# Sheet1.net
KiCad netlist of a schematic drawn in Altium Designer
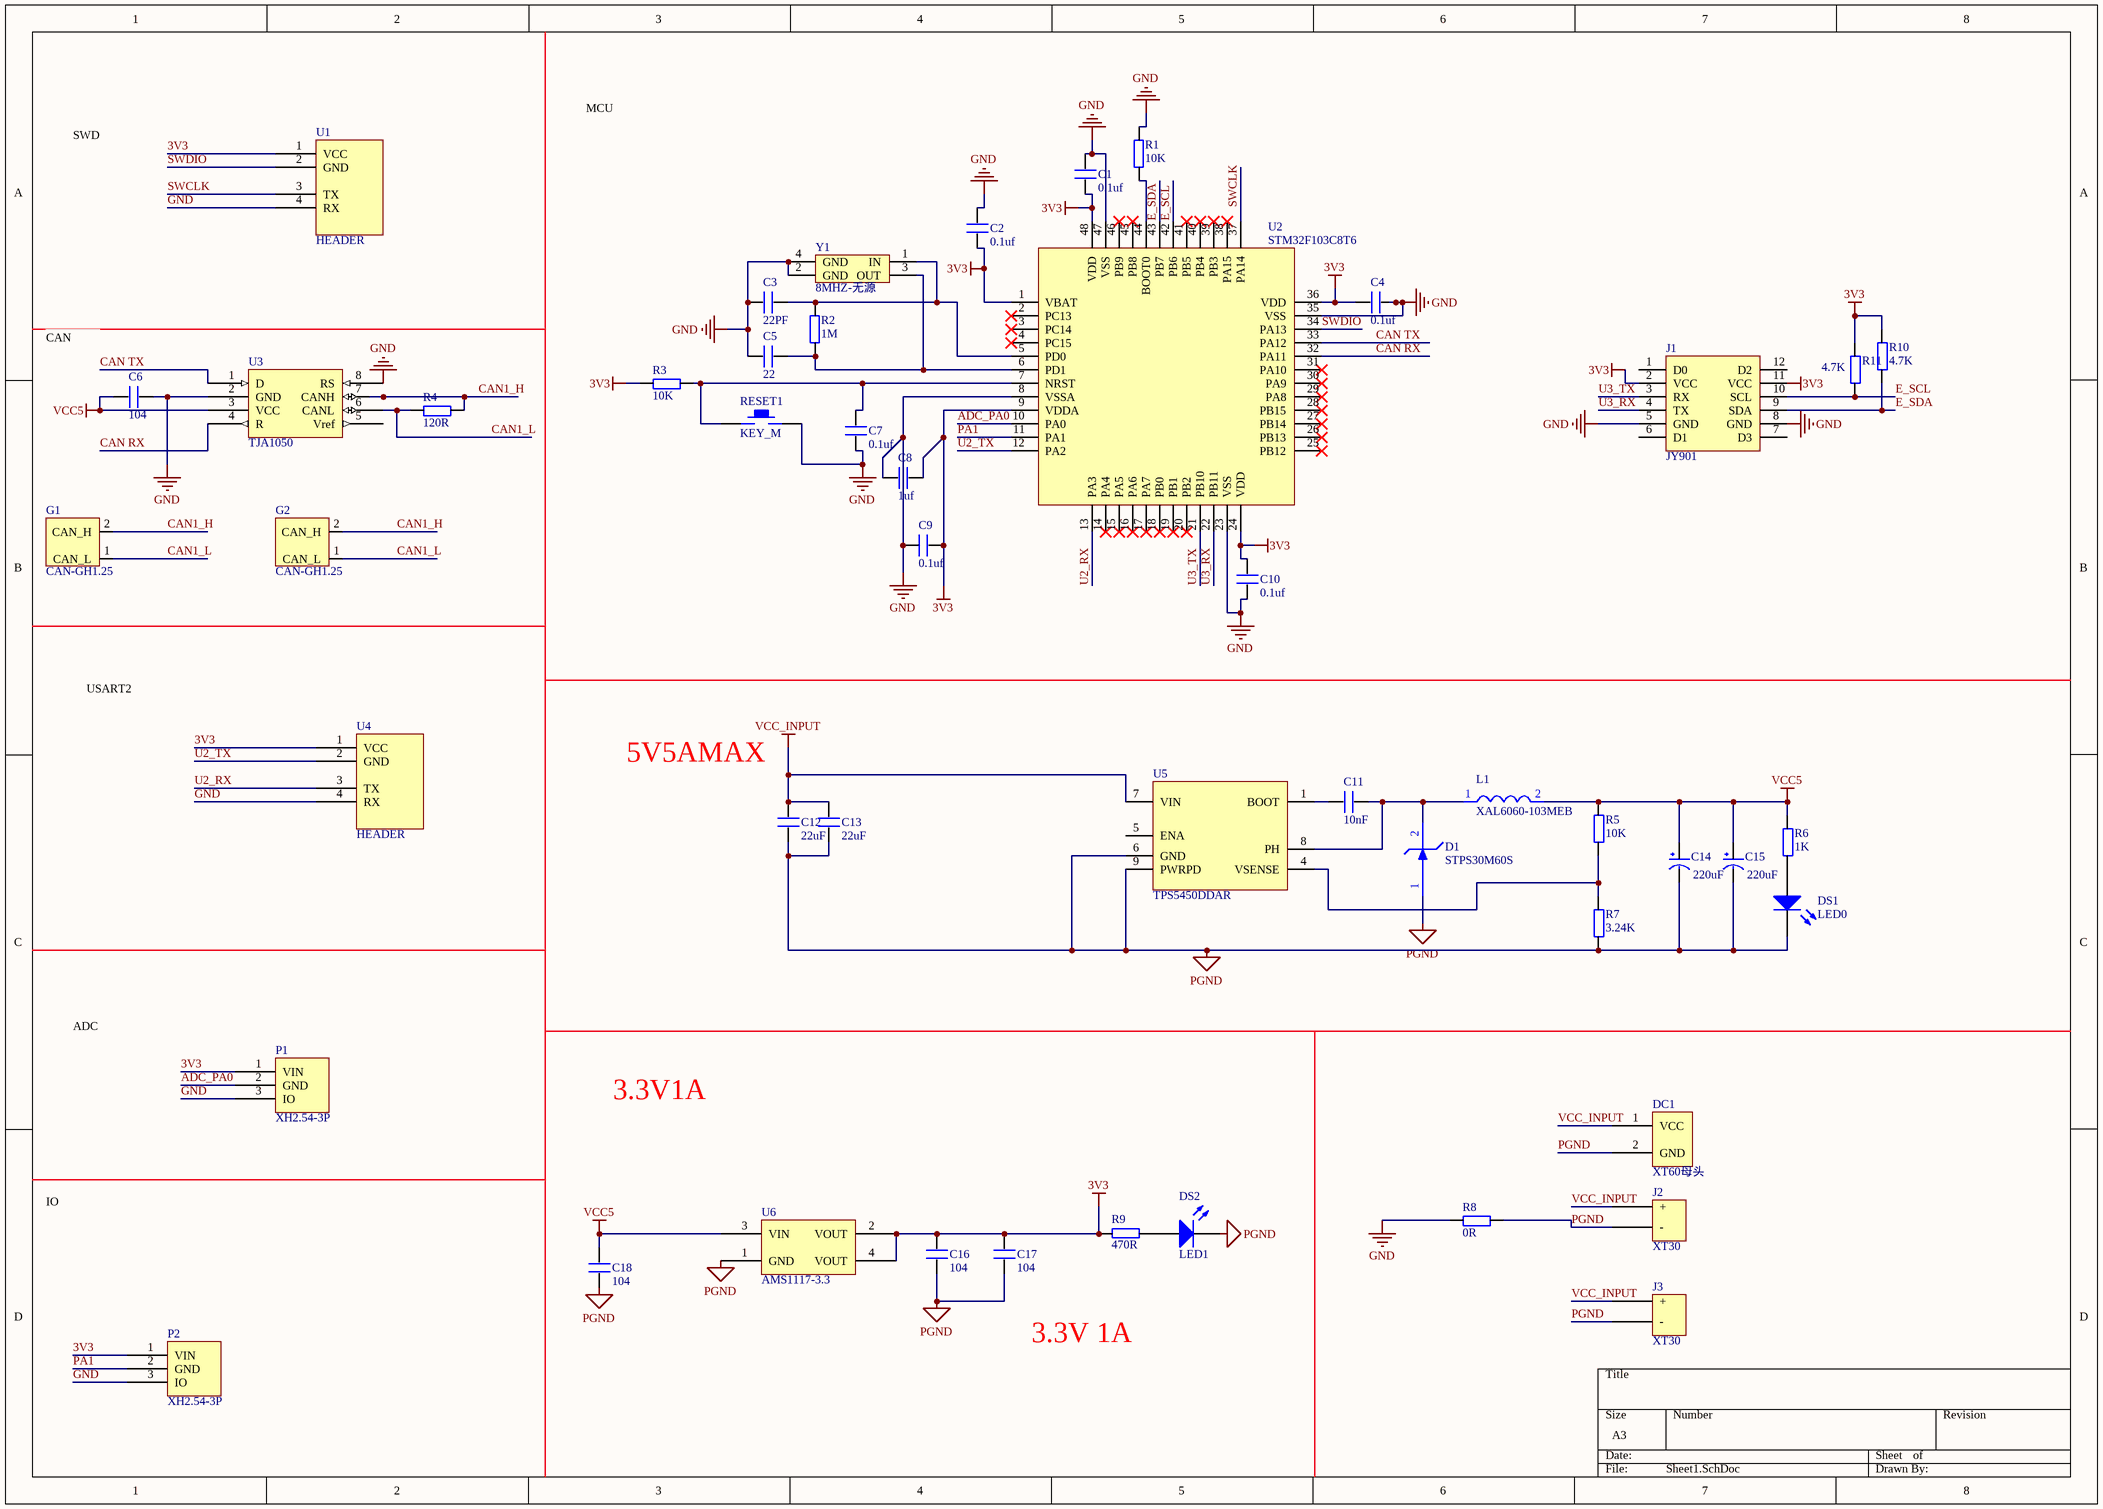
[diagram p0: Sheet1.SchDoc]

(export (version "E")
  (design (tool "Eeschema 10.0.6"))
  (components
    (comp (ref "C1") (value "0.1uf") (footprint "0603P") (libsource (lib "Explorer STM32F407封装库") (part "C")))
    (comp (ref "C2") (value "0.1uf") (footprint "0603P") (libsource (lib "Explorer STM32F407封装库") (part "C")))
    (comp (ref "C3") (value "22PF") (footprint "0603P") (libsource (lib "Explorer STM32F407封装库") (part "C")))
    (comp (ref "C4") (value "0.1uf") (footprint "0603P") (libsource (lib "Explorer STM32F407封装库") (part "C")))
    (comp (ref "C5") (value "22") (footprint "0603P") (libsource (lib "Explorer STM32F407封装库") (part "C")))
    (comp (ref "C6") (value "104") (footprint "0603P") (libsource (lib "Explorer STM32F407封装库") (part "C")))
    (comp (ref "C7") (value "0.1uf") (footprint "0603P") (libsource (lib "Explorer STM32F407封装库") (part "C")))
    (comp (ref "C8") (value "1uf") (footprint "0603P") (libsource (lib "Explorer STM32F407封装库") (part "C")))
    (comp (ref "C9") (value "0.1uf") (footprint "0603P") (libsource (lib "Explorer STM32F407封装库") (part "C")))
    (comp (ref "C10")
      (value "0.1uf")
      (footprint "0603P")
      (libsource (lib "Explorer STM32F407封装库") (part "C"))
    )
    (comp (ref "C11")
      (value "10nF")
      (footprint "0603P")
      (libsource (lib "Explorer STM32F407封装库_SCH") (part "C"))
    )
    (comp (ref "C12")
      (value "22uF")
      (footprint "0603P")
      (libsource (lib "Explorer STM32F407封装库_SCH") (part "C"))
    )
    (comp (ref "C13")
      (value "22uF")
      (footprint "0603P")
      (libsource (lib "Explorer STM32F407封装库_SCH") (part "C"))
    )
    (comp (ref "C14")
      (value "220uF")
      (footprint "CC6.56.5")
      (libsource (lib "Explorer STM32F407封装库") (part "CAP"))
    )
    (comp (ref "C15")
      (value "220uF")
      (footprint "CC6.56.5")
      (libsource (lib "Explorer STM32F407封装库") (part "CAP"))
    )
    (comp (ref "C16")
      (value "104")
      (footprint "0603P")
      (libsource (lib "Explorer STM32F407封装库_SCH") (part "C"))
    )
    (comp (ref "C17")
      (value "104")
      (footprint "0603P")
      (libsource (lib "Explorer STM32F407封装库_SCH") (part "C"))
    )
    (comp (ref "C18")
      (value "104")
      (footprint "0603P")
      (libsource (lib "Explorer STM32F407封装库_SCH") (part "C"))
    )
    (comp (ref "D1")
      (value "STPS30M60S")
      (footprint "STPS30M60S")
      (libsource (lib "SCHlib") (part "STPS30M60S"))
    )
    (comp (ref "DC1") (value "XT60母头") (footprint "XT60-母头") (libsource (lib "羽毛球团队") (part "XT60-母头")))
    (comp (ref "DS1")
      (value "LED0")
      (footprint "LED-0603-hm")
      (description "Typical RED, GREEN, YELLOW, AMBER GaAs LED")
      (fields (field (name "PUBLISHER") "Altium Limited"))
      (libsource (lib "Explorer STM32F407封装库") (part "LED2"))
    )
    (comp (ref "DS2")
      (value "LED1")
      (footprint "LED-0603-hm")
      (description "Typical RED, GREEN, YELLOW, AMBER GaAs LED")
      (fields (field (name "PUBLISHER") "Altium Limited"))
      (libsource (lib "Explorer STM32F407封装库") (part "LED2"))
    )
    (comp (ref "G1")
      (value "CAN-GH1.25")
      (footprint "GH1.25_1*2_lishi")
      (libsource (lib "SCHlib") (part "GH1.25-CAN"))
    )
    (comp (ref "G2")
      (value "CAN-GH1.25")
      (footprint "GH1.25_1*2_lishi")
      (libsource (lib "SCHlib") (part "GH1.25-CAN"))
    )
    (comp (ref "J1") (value "JY901") (footprint "JY901") (libsource (lib "Mini_Blimp") (part "JY901-PAD")))
    (comp (ref "J2") (value "XT30") (footprint "XT30") (libsource (lib "SCHlib") (part "XT30")))
    (comp (ref "J3") (value "XT30") (footprint "XT30") (libsource (lib "SCHlib") (part "XT30")))
    (comp (ref "L1")
      (value "XAL6060-103MEB")
      (footprint "XAL6060-103MEB")
      (libsource (lib "SCHlib") (part "贴片电感"))
    )
    (comp (ref "P1")
      (value "XH2.54-3P")
      (footprint "XH2.54插座-3P")
      (libsource (lib "羽毛球团队") (part "XH2.54插座-3P"))
    )
    (comp (ref "P2")
      (value "XH2.54-3P")
      (footprint "XH2.54插座-3P")
      (libsource (lib "羽毛球团队") (part "XH2.54插座-3P"))
    )
    (comp (ref "R1") (value "10K") (footprint "0603P") (libsource (lib "Explorer STM32F407封装库") (part "R")))
    (comp (ref "R2") (value "1M") (footprint "0603P") (libsource (lib "Explorer STM32F407封装库") (part "R")))
    (comp (ref "R3") (value "10K") (footprint "0603P") (libsource (lib "Explorer STM32F407封装库") (part "R")))
    (comp (ref "R4") (value "120R") (footprint "0603P") (libsource (lib "Explorer STM32F407封装库") (part "R")))
    (comp (ref "R5")
      (value "10K")
      (footprint "0603P")
      (libsource (lib "Explorer STM32F407封装库_SCH") (part "R"))
    )
    (comp (ref "R6")
      (value "1K")
      (footprint "0603P")
      (libsource (lib "Explorer STM32F407封装库_SCH") (part "R"))
    )
    (comp (ref "R7")
      (value "3.24K")
      (footprint "0603P")
      (libsource (lib "Explorer STM32F407封装库_SCH") (part "R"))
    )
    (comp (ref "R8") (value "0R") (footprint "0603P") (libsource (lib "Explorer STM32F407封装库") (part "R")))
    (comp (ref "R9")
      (value "470R")
      (footprint "0603P")
      (libsource (lib "Explorer STM32F407封装库_SCH") (part "R"))
    )
    (comp (ref "R10") (value "4.7K") (footprint "0603P") (libsource (lib "Explorer STM32F407封装库") (part "R")))
    (comp (ref "R11") (value "4.7K") (footprint "0603P") (libsource (lib "Explorer STM32F407封装库") (part "R")))
    (comp (ref "RESET1")
      (value "KEY_M")
      (footprint "KEY_M")
      (libsource (lib "Explorer STM32F407封装库_SCH") (part "KEY_M"))
    )
    (comp (ref "U1")
      (value "HEADER")
      (footprint "XH2.54插座-4P")
      (libsource (lib "羽毛球团队") (part "XH2.54插座-4P"))
    )
    (comp (ref "U2")
      (value "STM32F103C8T6")
      (footprint "LQFP-48_7x7x05P")
      (libsource (lib "RoboFly") (part "STM32F103C8T6"))
    )
    (comp (ref "U3")
      (value "TJA1050")
      (footprint "SOP-8")
      (libsource (lib "Explorer STM32F407封装库") (part "SN65HVD230D"))
    )
    (comp (ref "U4")
      (value "HEADER")
      (footprint "XH2.54插座-4P")
      (libsource (lib "羽毛球团队") (part "XH2.54插座-4P"))
    )
    (comp (ref "U5") (value "TPS5450DDAR") (footprint "TPS5450") (libsource (lib "SCHlib") (part "TPS5450")))
    (comp (ref "U6") (value "AMS1117-3.3") (footprint "SOT223") (libsource (lib "74hc595") (part "AMS1117")))
    (comp (ref "Y1")
      (value "8MHZ-无源")
      (footprint "XTAL3225   无源")
      (libsource (lib "SCHlib") (part "XTAL-3225"))
    )
  )
  (nets
    (net (code "1") (name "/ADC_PA0") (class "Default")
      (node (ref "P1") (pin "2") (pinfunction "GND_2") (pintype "passive"))
      (node (ref "U2") (pin "10") (pinfunction "PA0_10") (pintype "passive"))
    )
    (net (code "2") (name "/CAN RX") (class "Default")
      (node (ref "U2") (pin "32") (pinfunction "PA11_32") (pintype "passive"))
      (node (ref "U3") (pin "4") (pinfunction "R_4") (pintype "output"))
    )
    (net (code "3") (name "/CAN TX") (class "Default")
      (node (ref "U2") (pin "33") (pinfunction "PA12_33") (pintype "passive"))
      (node (ref "U3") (pin "1") (pinfunction "D_1") (pintype "input"))
    )
    (net (code "4") (name "/CAN1_H") (class "Default")
      (node (ref "G1") (pin "2") (pinfunction "CAN_H_2") (pintype "passive"))
      (node (ref "G2") (pin "2") (pinfunction "CAN_H_2") (pintype "passive"))
      (node (ref "R4") (pin "2") (pintype "passive"))
      (node (ref "U3") (pin "7") (pinfunction "CANH_7") (pintype "bidirectional"))
    )
    (net (code "5") (name "/CAN1_L") (class "Default")
      (node (ref "G1") (pin "1") (pinfunction "CAN_L_1") (pintype "passive"))
      (node (ref "G2") (pin "1") (pinfunction "CAN_L_1") (pintype "passive"))
      (node (ref "R4") (pin "1") (pintype "passive"))
      (node (ref "U3") (pin "6") (pinfunction "CANL_6") (pintype "bidirectional"))
    )
    (net (code "6") (name "/E_SCL") (class "Default")
      (node (ref "J1") (pin "10") (pinfunction "SCL_10") (pintype "passive"))
      (node (ref "R11") (pin "1") (pintype "passive"))
      (node (ref "U2") (pin "42") (pinfunction "PB6_42") (pintype "passive"))
    )
    (net (code "7") (name "/E_SDA") (class "Default")
      (node (ref "J1") (pin "9") (pinfunction "SDA_9") (pintype "passive"))
      (node (ref "R10") (pin "1") (pintype "passive"))
      (node (ref "U2") (pin "43") (pinfunction "PB7_43") (pintype "passive"))
    )
    (net (code "8") (name "/PA1") (class "Default")
      (node (ref "P2") (pin "2") (pinfunction "GND_2") (pintype "passive"))
      (node (ref "U2") (pin "11") (pinfunction "PA1_11") (pintype "passive"))
    )
    (net (code "9") (name "/SWCLK") (class "Default")
      (node (ref "U1") (pin "3") (pinfunction "TX_3") (pintype "passive"))
      (node (ref "U2") (pin "37") (pinfunction "PA14_37") (pintype "passive"))
    )
    (net (code "10") (name "/SWDIO") (class "Default")
      (node (ref "U1") (pin "2") (pinfunction "GND_2") (pintype "passive"))
      (node (ref "U2") (pin "34") (pinfunction "PA13_34") (pintype "passive"))
    )
    (net (code "11") (name "/U2_RX") (class "Default")
      (node (ref "U2") (pin "13") (pinfunction "PA3_13") (pintype "passive"))
      (node (ref "U4") (pin "3") (pinfunction "TX_3") (pintype "passive"))
    )
    (net (code "12") (name "/U2_TX") (class "Default")
      (node (ref "U2") (pin "12") (pinfunction "PA2_12") (pintype "passive"))
      (node (ref "U4") (pin "2") (pinfunction "GND_2") (pintype "passive"))
    )
    (net (code "13") (name "/U3_RX") (class "Default")
      (node (ref "J1") (pin "4") (pinfunction "TX_4") (pintype "passive"))
      (node (ref "U2") (pin "22") (pinfunction "PB11_22") (pintype "passive"))
    )
    (net (code "14") (name "/U3_TX") (class "Default")
      (node (ref "J1") (pin "3") (pinfunction "RX_3") (pintype "passive"))
      (node (ref "U2") (pin "21") (pinfunction "PB10_21") (pintype "passive"))
    )
    (net (code "15") (name "3V3") (class "Default")
      (node (ref "C1") (pin "1") (pintype "passive"))
      (node (ref "C10") (pin "2") (pintype "passive"))
      (node (ref "C16") (pin "2") (pintype "passive"))
      (node (ref "C17") (pin "2") (pintype "passive"))
      (node (ref "C2") (pin "1") (pintype "passive"))
      (node (ref "C4") (pin "2") (pintype "passive"))
      (node (ref "C8") (pin "1") (pintype "passive"))
      (node (ref "C9") (pin "1") (pintype "passive"))
      (node (ref "J1") (pin "11") (pinfunction "VCC_11") (pintype "passive"))
      (node (ref "J1") (pin "2") (pinfunction "VCC_2") (pintype "passive"))
      (node (ref "P1") (pin "1") (pinfunction "VIN_1") (pintype "passive"))
      (node (ref "P2") (pin "1") (pinfunction "VIN_1") (pintype "passive"))
      (node (ref "R10") (pin "2") (pintype "passive"))
      (node (ref "R11") (pin "2") (pintype "passive"))
      (node (ref "R3") (pin "1") (pintype "passive"))
      (node (ref "R9") (pin "2") (pintype "passive"))
      (node (ref "U1") (pin "1") (pinfunction "VCC_1") (pintype "passive"))
      (node (ref "U2") (pin "1") (pinfunction "VBAT_1") (pintype "passive"))
      (node (ref "U2") (pin "24") (pinfunction "VDD_24") (pintype "passive"))
      (node (ref "U2") (pin "36") (pinfunction "VDD_36") (pintype "passive"))
      (node (ref "U2") (pin "48") (pinfunction "VDD_48") (pintype "passive"))
      (node (ref "U2") (pin "9") (pinfunction "VDDA_9") (pintype "passive"))
      (node (ref "U4") (pin "1") (pinfunction "VCC_1") (pintype "passive"))
      (node (ref "U6") (pin "2") (pinfunction "VOUT_2") (pintype "passive"))
      (node (ref "U6") (pin "4") (pinfunction "VOUT_4") (pintype "passive"))
    )
    (net (code "16") (name "GND") (class "Default")
      (node (ref "C1") (pin "2") (pintype "passive"))
      (node (ref "C10") (pin "1") (pintype "passive"))
      (node (ref "C2") (pin "2") (pintype "passive"))
      (node (ref "C3") (pin "2") (pintype "passive"))
      (node (ref "C4") (pin "1") (pintype "passive"))
      (node (ref "C5") (pin "2") (pintype "passive"))
      (node (ref "C6") (pin "2") (pintype "passive"))
      (node (ref "C7") (pin "1") (pintype "passive"))
      (node (ref "C8") (pin "2") (pintype "passive"))
      (node (ref "C9") (pin "2") (pintype "passive"))
      (node (ref "J1") (pin "5") (pinfunction "GND_5") (pintype "passive"))
      (node (ref "J1") (pin "8") (pinfunction "GND_8") (pintype "passive"))
      (node (ref "P1") (pin "3") (pinfunction "IO_3") (pintype "passive"))
      (node (ref "P2") (pin "3") (pinfunction "IO_3") (pintype "passive"))
      (node (ref "R1") (pin "1") (pintype "passive"))
      (node (ref "R8") (pin "1") (pintype "passive"))
      (node (ref "RESET1") (pin "2") (pinfunction "2_2") (pintype "passive"))
      (node (ref "U1") (pin "4") (pinfunction "RX_4") (pintype "passive"))
      (node (ref "U2") (pin "23") (pinfunction "VSS_23") (pintype "passive"))
      (node (ref "U2") (pin "35") (pinfunction "VSS_35") (pintype "passive"))
      (node (ref "U2") (pin "47") (pinfunction "VSS_47") (pintype "passive"))
      (node (ref "U2") (pin "8") (pinfunction "VSSA_8") (pintype "passive"))
      (node (ref "U3") (pin "2") (pinfunction "GND_2") (pintype "power_in"))
      (node (ref "U3") (pin "8") (pinfunction "RS_8") (pintype "input"))
      (node (ref "U4") (pin "4") (pinfunction "RX_4") (pintype "passive"))
      (node (ref "Y1") (pin "2") (pinfunction "GND_2") (pintype "passive"))
      (node (ref "Y1") (pin "4") (pinfunction "GND_4") (pintype "passive"))
    )
    (net (code "17") (name "Net-(D1-K)") (class "Default")
      (node (ref "C11") (pin "2") (pintype "passive"))
      (node (ref "D1") (pin "2") (pinfunction "K_2") (pintype "passive"))
      (node (ref "L1") (pin "1") (pinfunction "VIN_1") (pintype "passive"))
      (node (ref "U5") (pin "8") (pinfunction "PH_8") (pintype "passive"))
    )
    (net (code "18") (name "Net-(DS1-A)") (class "Default")
      (node (ref "DS1") (pin "1") (pinfunction "A_1") (pintype "passive"))
      (node (ref "R6") (pin "1") (pintype "passive"))
    )
    (net (code "19") (name "Net-(DS2-A)") (class "Default")
      (node (ref "DS2") (pin "1") (pinfunction "A_1") (pintype "passive"))
      (node (ref "R9") (pin "1") (pintype "passive"))
    )
    (net (code "20") (name "Net-(U2-BOOT0)") (class "Default")
      (node (ref "R1") (pin "2") (pintype "passive"))
      (node (ref "U2") (pin "44") (pinfunction "BOOT0_44") (pintype "passive"))
    )
    (net (code "21") (name "Net-(U2-NRST)") (class "Default")
      (node (ref "C7") (pin "2") (pintype "passive"))
      (node (ref "R3") (pin "2") (pintype "passive"))
      (node (ref "RESET1") (pin "1") (pinfunction "1_1") (pintype "passive"))
      (node (ref "U2") (pin "7") (pinfunction "NRST_7") (pintype "passive"))
    )
    (net (code "22") (name "Net-(U2-PD0)") (class "Default")
      (node (ref "C3") (pin "1") (pintype "passive"))
      (node (ref "R2") (pin "1") (pintype "passive"))
      (node (ref "U2") (pin "5") (pinfunction "PD0_5") (pintype "passive"))
      (node (ref "Y1") (pin "1") (pinfunction "IN_1") (pintype "passive"))
    )
    (net (code "23") (name "Net-(U2-PD1)") (class "Default")
      (node (ref "C5") (pin "1") (pintype "passive"))
      (node (ref "R2") (pin "2") (pintype "passive"))
      (node (ref "U2") (pin "6") (pinfunction "PD1_6") (pintype "passive"))
      (node (ref "Y1") (pin "3") (pinfunction "OUT_3") (pintype "passive"))
    )
    (net (code "24") (name "Net-(U5-BOOT)") (class "Default")
      (node (ref "C11") (pin "1") (pintype "passive"))
      (node (ref "U5") (pin "1") (pinfunction "BOOT_1") (pintype "passive"))
    )
    (net (code "25") (name "Net-(U5-VSENSE)") (class "Default")
      (node (ref "R5") (pin "1") (pintype "passive"))
      (node (ref "R7") (pin "2") (pintype "passive"))
      (node (ref "U5") (pin "4") (pinfunction "VSENSE_4") (pintype "passive"))
    )
    (net (code "26") (name "PGND") (class "Default")
      (node (ref "C12") (pin "1") (pintype "passive"))
      (node (ref "C13") (pin "1") (pintype "passive"))
      (node (ref "C14") (pin "2") (pinfunction "GND_2") (pintype "passive"))
      (node (ref "C15") (pin "2") (pinfunction "GND_2") (pintype "passive"))
      (node (ref "C16") (pin "1") (pintype "passive"))
      (node (ref "C17") (pin "1") (pintype "passive"))
      (node (ref "C18") (pin "1") (pintype "passive"))
      (node (ref "D1") (pin "1") (pinfunction "A_1") (pintype "passive"))
      (node (ref "DC1") (pin "2") (pinfunction "GND_2") (pintype "passive"))
      (node (ref "DS1") (pin "2") (pinfunction "K_2") (pintype "passive"))
      (node (ref "DS2") (pin "2") (pinfunction "K_2") (pintype "passive"))
      (node (ref "J2") (pin "0") (pinfunction "-_0") (pintype "passive"))
      (node (ref "J3") (pin "0") (pinfunction "-_0") (pintype "passive"))
      (node (ref "R7") (pin "1") (pintype "passive"))
      (node (ref "R8") (pin "2") (pintype "passive"))
      (node (ref "U5") (pin "6") (pinfunction "GND_6") (pintype "passive"))
      (node (ref "U5") (pin "9") (pinfunction "PWRPD_9") (pintype "passive"))
      (node (ref "U6") (pin "1") (pinfunction "GND_1") (pintype "passive"))
    )
    (net (code "27") (name "VCC5") (class "Default")
      (node (ref "C14") (pin "1") (pinfunction "VCC_1") (pintype "passive"))
      (node (ref "C15") (pin "1") (pinfunction "VCC_1") (pintype "passive"))
      (node (ref "C18") (pin "2") (pintype "passive"))
      (node (ref "C6") (pin "1") (pintype "passive"))
      (node (ref "L1") (pin "2") (pinfunction "VIN_2") (pintype "passive"))
      (node (ref "R5") (pin "2") (pintype "passive"))
      (node (ref "R6") (pin "2") (pintype "passive"))
      (node (ref "U3") (pin "3") (pinfunction "VCC_3") (pintype "power_in"))
      (node (ref "U6") (pin "3") (pinfunction "VIN_3") (pintype "passive"))
    )
    (net (code "28") (name "VCC_INPUT") (class "Default")
      (node (ref "C12") (pin "2") (pintype "passive"))
      (node (ref "C13") (pin "2") (pintype "passive"))
      (node (ref "DC1") (pin "1") (pinfunction "VCC_1") (pintype "passive"))
      (node (ref "J2") (pin "1") (pinfunction "+_1") (pintype "passive"))
      (node (ref "J3") (pin "1") (pinfunction "+_1") (pintype "passive"))
      (node (ref "U5") (pin "7") (pinfunction "VIN_7") (pintype "passive"))
    )
    (net (code "29") (name "unconnected-(J1-D0-Pad1)") (class "Default")
      (node (ref "J1") (pin "1") (pinfunction "D0_1") (pintype "passive"))
    )
    (net (code "30") (name "unconnected-(J1-D1-Pad6)") (class "Default")
      (node (ref "J1") (pin "6") (pinfunction "D1_6") (pintype "passive"))
    )
    (net (code "31") (name "unconnected-(J1-D2-Pad12)") (class "Default")
      (node (ref "J1") (pin "12") (pinfunction "D2_12") (pintype "passive"))
    )
    (net (code "32") (name "unconnected-(J1-D3-Pad7)") (class "Default")
      (node (ref "J1") (pin "7") (pinfunction "D3_7") (pintype "passive"))
    )
    (net (code "33") (name "unconnected-(U2-PA4-Pad14)") (class "Default")
      (node (ref "U2") (pin "14") (pinfunction "PA4_14") (pintype "passive+no_connect"))
    )
    (net (code "34") (name "unconnected-(U2-PA5-Pad15)") (class "Default")
      (node (ref "U2") (pin "15") (pinfunction "PA5_15") (pintype "passive+no_connect"))
    )
    (net (code "35") (name "unconnected-(U2-PA6-Pad16)") (class "Default")
      (node (ref "U2") (pin "16") (pinfunction "PA6_16") (pintype "passive+no_connect"))
    )
    (net (code "36") (name "unconnected-(U2-PA7-Pad17)") (class "Default")
      (node (ref "U2") (pin "17") (pinfunction "PA7_17") (pintype "passive+no_connect"))
    )
    (net (code "37") (name "unconnected-(U2-PA8-Pad29)") (class "Default")
      (node (ref "U2") (pin "29") (pinfunction "PA8_29") (pintype "passive+no_connect"))
    )
    (net (code "38") (name "unconnected-(U2-PA9-Pad30)") (class "Default")
      (node (ref "U2") (pin "30") (pinfunction "PA9_30") (pintype "passive+no_connect"))
    )
    (net (code "39") (name "unconnected-(U2-PA10-Pad31)") (class "Default")
      (node (ref "U2") (pin "31") (pinfunction "PA10_31") (pintype "passive+no_connect"))
    )
    (net (code "40") (name "unconnected-(U2-PA15-Pad38)") (class "Default")
      (node (ref "U2") (pin "38") (pinfunction "PA15_38") (pintype "passive+no_connect"))
    )
    (net (code "41") (name "unconnected-(U2-PB0-Pad18)") (class "Default")
      (node (ref "U2") (pin "18") (pinfunction "PB0_18") (pintype "passive+no_connect"))
    )
    (net (code "42") (name "unconnected-(U2-PB1-Pad19)") (class "Default")
      (node (ref "U2") (pin "19") (pinfunction "PB1_19") (pintype "passive+no_connect"))
    )
    (net (code "43") (name "unconnected-(U2-PB2-Pad20)") (class "Default")
      (node (ref "U2") (pin "20") (pinfunction "PB2_20") (pintype "passive+no_connect"))
    )
    (net (code "44") (name "unconnected-(U2-PB3-Pad39)") (class "Default")
      (node (ref "U2") (pin "39") (pinfunction "PB3_39") (pintype "passive+no_connect"))
    )
    (net (code "45") (name "unconnected-(U2-PB4-Pad40)") (class "Default")
      (node (ref "U2") (pin "40") (pinfunction "PB4_40") (pintype "passive+no_connect"))
    )
    (net (code "46") (name "unconnected-(U2-PB5-Pad41)") (class "Default")
      (node (ref "U2") (pin "41") (pinfunction "PB5_41") (pintype "passive+no_connect"))
    )
    (net (code "47") (name "unconnected-(U2-PB8-Pad45)") (class "Default")
      (node (ref "U2") (pin "45") (pinfunction "PB8_45") (pintype "passive+no_connect"))
    )
    (net (code "48") (name "unconnected-(U2-PB9-Pad46)") (class "Default")
      (node (ref "U2") (pin "46") (pinfunction "PB9_46") (pintype "passive+no_connect"))
    )
    (net (code "49") (name "unconnected-(U2-PB12-Pad25)") (class "Default")
      (node (ref "U2") (pin "25") (pinfunction "PB12_25") (pintype "passive+no_connect"))
    )
    (net (code "50") (name "unconnected-(U2-PB13-Pad26)") (class "Default")
      (node (ref "U2") (pin "26") (pinfunction "PB13_26") (pintype "passive+no_connect"))
    )
    (net (code "51") (name "unconnected-(U2-PB14-Pad27)") (class "Default")
      (node (ref "U2") (pin "27") (pinfunction "PB14_27") (pintype "passive+no_connect"))
    )
    (net (code "52") (name "unconnected-(U2-PB15-Pad28)") (class "Default")
      (node (ref "U2") (pin "28") (pinfunction "PB15_28") (pintype "passive+no_connect"))
    )
    (net (code "53") (name "unconnected-(U2-PC13-Pad2)") (class "Default")
      (node (ref "U2") (pin "2") (pinfunction "PC13_2") (pintype "passive+no_connect"))
    )
    (net (code "54") (name "unconnected-(U2-PC14-Pad3)") (class "Default")
      (node (ref "U2") (pin "3") (pinfunction "PC14_3") (pintype "passive+no_connect"))
    )
    (net (code "55") (name "unconnected-(U2-PC15-Pad4)") (class "Default")
      (node (ref "U2") (pin "4") (pinfunction "PC15_4") (pintype "passive+no_connect"))
    )
    (net (code "56") (name "unconnected-(U3-Vref-Pad5)") (class "Default")
      (node (ref "U3") (pin "5") (pinfunction "Vref_5") (pintype "output"))
    )
    (net (code "57") (name "unconnected-(U5-ENA-Pad5)") (class "Default")
      (node (ref "U5") (pin "5") (pinfunction "ENA_5") (pintype "passive"))
    )
  )
)
